# Sheet_2.net
KiCad netlist of a schematic drawn in EasyEDA
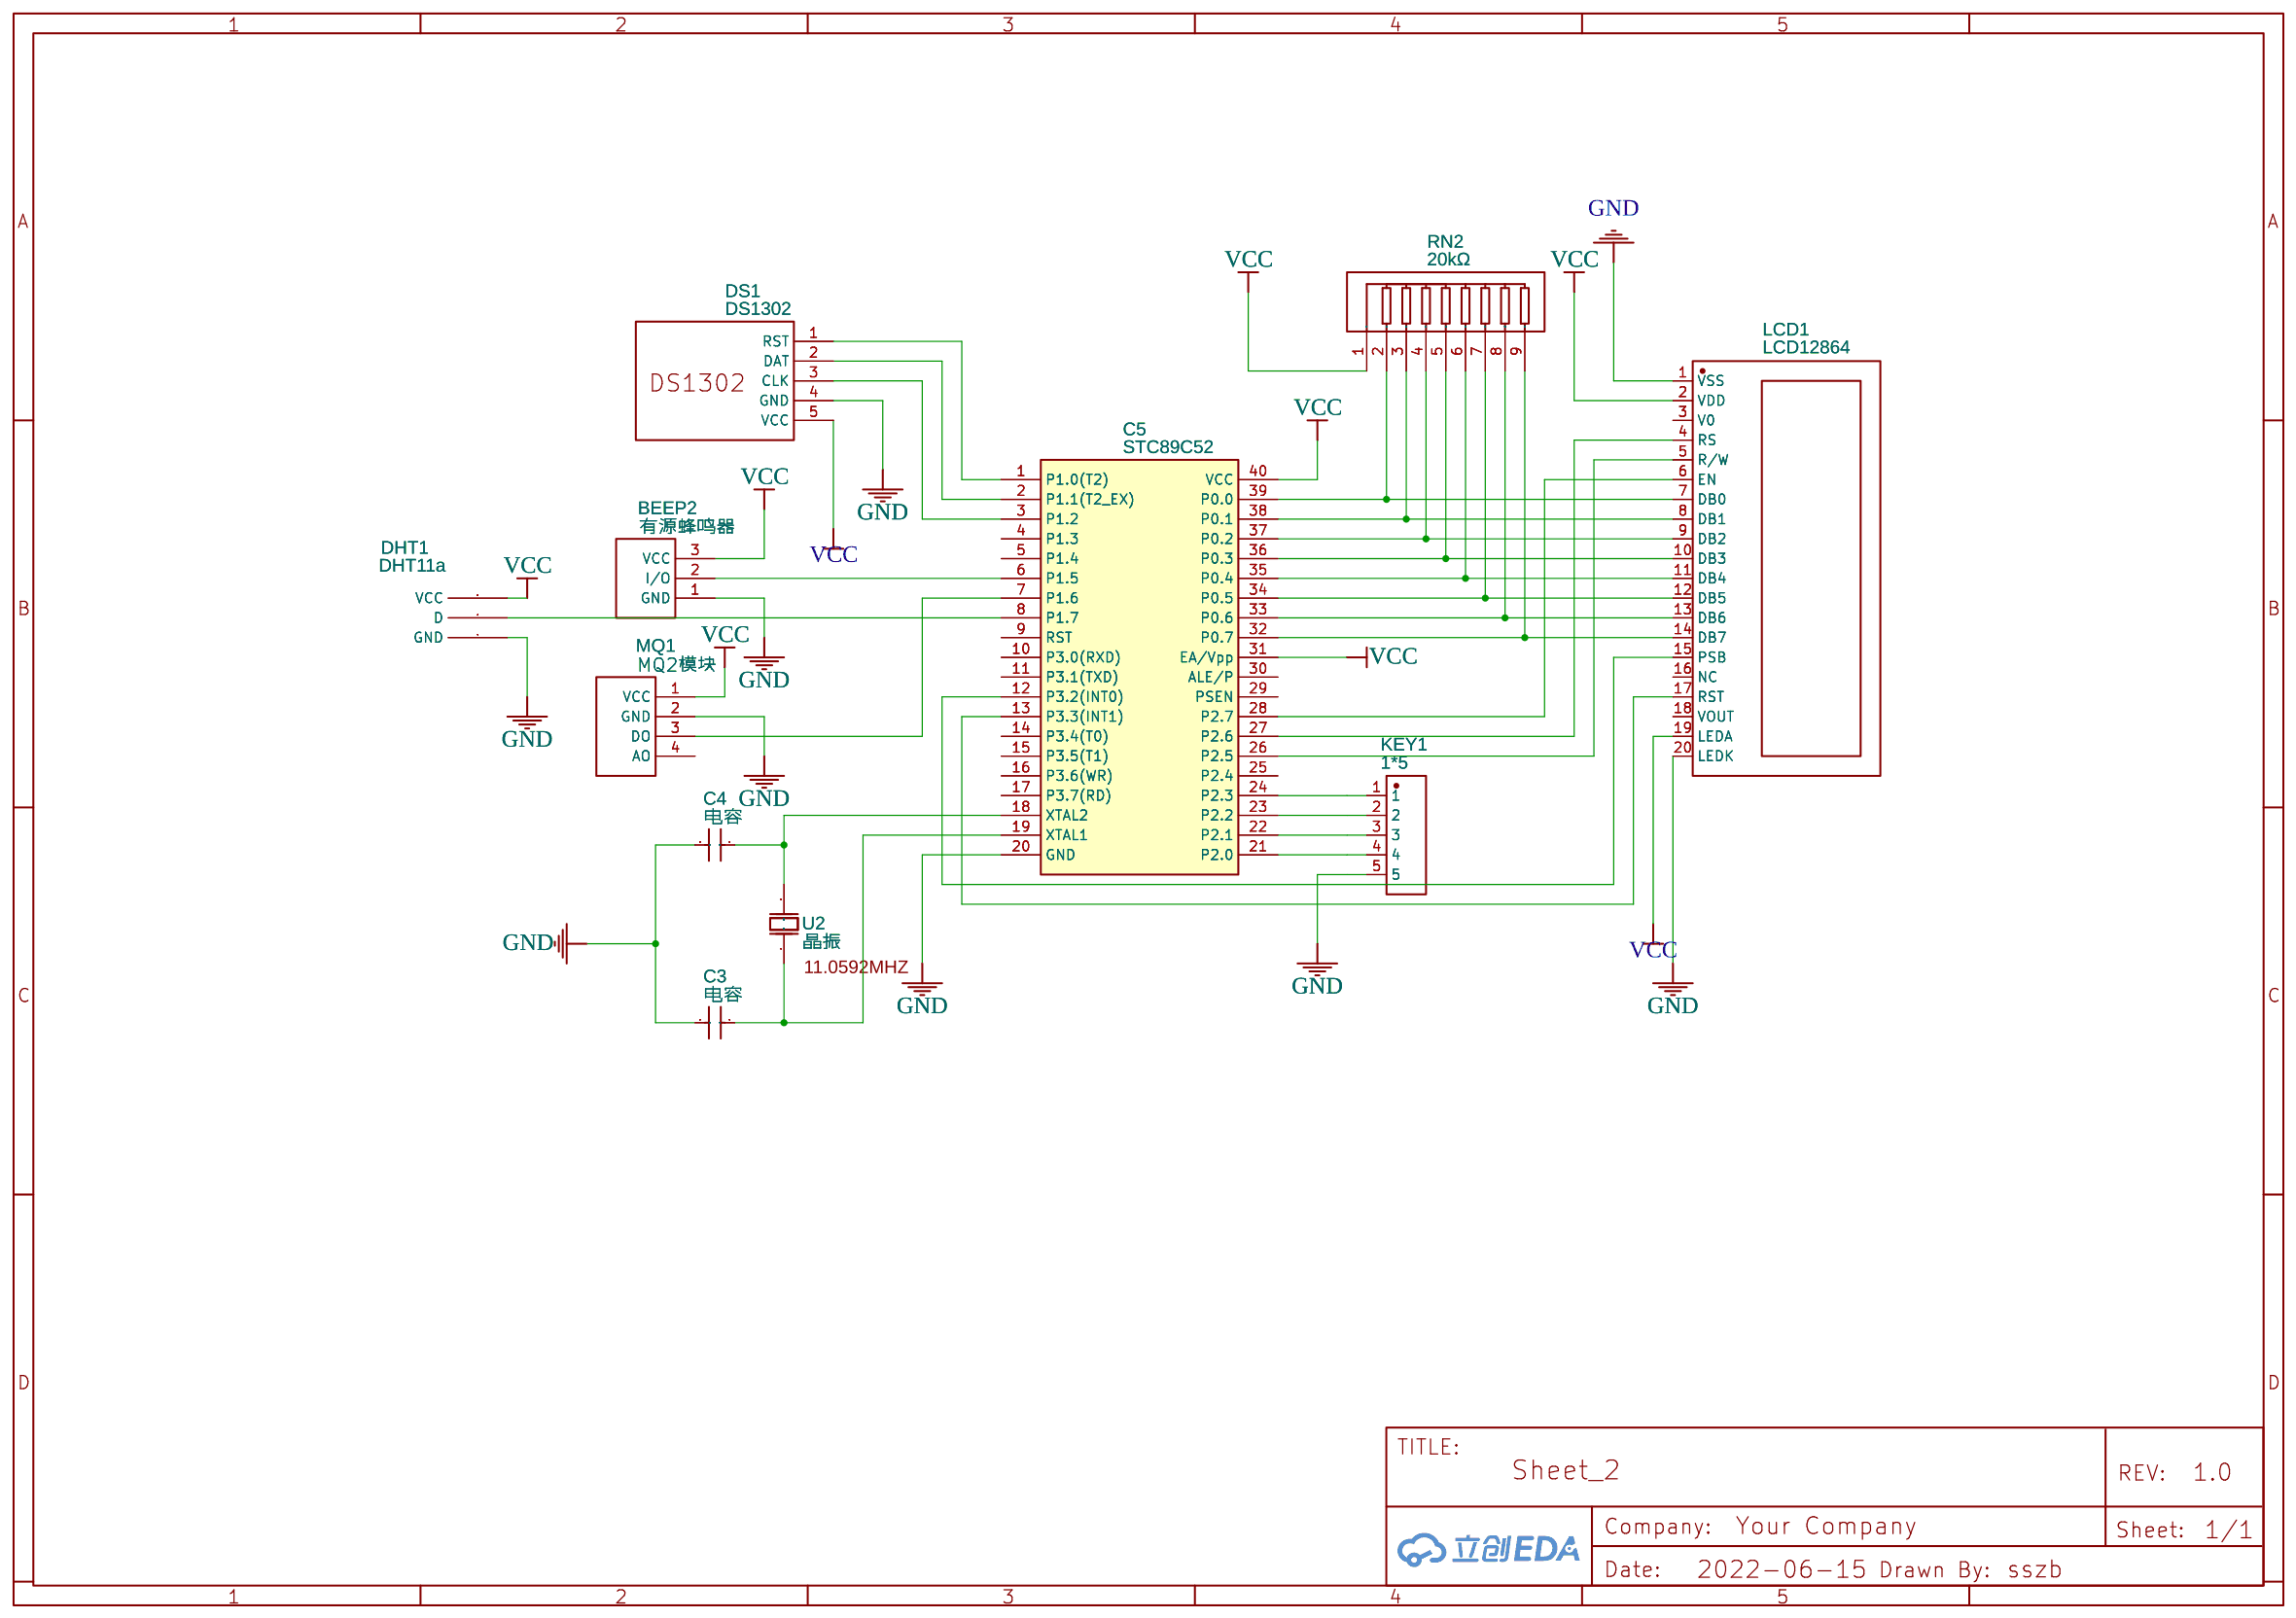
[diagram p0: schematic sheet]

(export (version "E")
  (design (tool "Eeschema 10.0.6"))
  (components
    (comp (ref "BEEP2") (value "有源蜂鸣器") (libsource (lib "") (part "有源蜂鸣器")))
    (comp (ref "C3") (value "电容") (libsource (lib "") (part "电容")))
    (comp (ref "C4") (value "电容") (libsource (lib "") (part "电容")))
    (comp (ref "C5") (value "STC89C52") (libsource (lib "") (part "STC89C52")))
    (comp (ref "DHT1")
      (value "DHT11a")
      (fields (field (name "BOM_Manufacturer Part") "模块DHT11开关模块模块DHT11度温湿湿度度传感器模块温湿"))
      (libsource (lib "") (part "温湿度传感器DHT11a"))
    )
    (comp (ref "DS1") (value "DS1302") (libsource (lib "") (part "DS1302")))
    (comp (ref "KEY1") (value "1*5") (libsource (lib "") (part "1*5")))
    (comp (ref "LCD1") (value "LCD12864") (libsource (lib "") (part "LCD12864")))
    (comp (ref "MQ1") (value "MQ2模块") (libsource (lib "") (part "MQ2模块")))
    (comp (ref "RN2")
      (value "20kΩ")
      (fields (field (name "BOM_Manufacturer Part") "A09-203JP") (field (name "BOM_Supplier Part") "C30847"))
      (libsource (lib "") (part "排阻"))
    )
    (comp (ref "U2") (value "晶振") (libsource (lib "") (part "晶振")))
  )
  (nets
    (net (code "1") (name "GND") (class "Default")
      (node (ref "BEEP2") (pin "1") (pinfunction "GND_1") (pintype "unspecified"))
      (node (ref "C3") (pin "1") (pinfunction "1_1") (pintype "unspecified"))
      (node (ref "C4") (pin "1") (pinfunction "1_1") (pintype "unspecified"))
      (node (ref "C5") (pin "20") (pinfunction "GND_20") (pintype "unspecified"))
      (node (ref "DHT1") (pin "1") (pinfunction "GND_1") (pintype "unspecified"))
      (node (ref "DS1") (pin "4") (pinfunction "GND_4") (pintype "unspecified"))
      (node (ref "KEY1") (pin "5") (pinfunction "5_5") (pintype "unspecified"))
      (node (ref "LCD1") (pin "1") (pinfunction "VSS_1") (pintype "unspecified"))
      (node (ref "LCD1") (pin "20") (pinfunction "LEDK_20") (pintype "unspecified"))
      (node (ref "MQ1") (pin "2") (pinfunction "GND_2") (pintype "unspecified"))
    )
    (net (code "2") (name "Net-(BEEP2-I{slash}O)") (class "Default")
      (node (ref "BEEP2") (pin "2") (pinfunction "I/O_2") (pintype "unspecified"))
      (node (ref "C5") (pin "6") (pinfunction "P1.5_6") (pintype "unspecified"))
    )
    (net (code "3") (name "Net-(C5-P0.0)") (class "Default")
      (node (ref "C5") (pin "39") (pinfunction "P0.0_39") (pintype "unspecified"))
      (node (ref "LCD1") (pin "7") (pinfunction "DB0_7") (pintype "unspecified"))
      (node (ref "RN2") (pin "2") (pinfunction "2_2") (pintype "unspecified"))
    )
    (net (code "4") (name "Net-(C5-P0.1)") (class "Default")
      (node (ref "C5") (pin "38") (pinfunction "P0.1_38") (pintype "unspecified"))
      (node (ref "LCD1") (pin "8") (pinfunction "DB1_8") (pintype "unspecified"))
      (node (ref "RN2") (pin "3") (pinfunction "3_3") (pintype "unspecified"))
    )
    (net (code "5") (name "Net-(C5-P0.2)") (class "Default")
      (node (ref "C5") (pin "37") (pinfunction "P0.2_37") (pintype "unspecified"))
      (node (ref "LCD1") (pin "9") (pinfunction "DB2_9") (pintype "unspecified"))
      (node (ref "RN2") (pin "4") (pinfunction "4_4") (pintype "unspecified"))
    )
    (net (code "6") (name "Net-(C5-P0.3)") (class "Default")
      (node (ref "C5") (pin "36") (pinfunction "P0.3_36") (pintype "unspecified"))
      (node (ref "LCD1") (pin "10") (pinfunction "DB3_10") (pintype "unspecified"))
      (node (ref "RN2") (pin "5") (pinfunction "5_5") (pintype "unspecified"))
    )
    (net (code "7") (name "Net-(C5-P0.4)") (class "Default")
      (node (ref "C5") (pin "35") (pinfunction "P0.4_35") (pintype "unspecified"))
      (node (ref "LCD1") (pin "11") (pinfunction "DB4_11") (pintype "unspecified"))
      (node (ref "RN2") (pin "6") (pinfunction "6_6") (pintype "unspecified"))
    )
    (net (code "8") (name "Net-(C5-P0.5)") (class "Default")
      (node (ref "C5") (pin "34") (pinfunction "P0.5_34") (pintype "unspecified"))
      (node (ref "LCD1") (pin "12") (pinfunction "DB5_12") (pintype "unspecified"))
      (node (ref "RN2") (pin "7") (pinfunction "7_7") (pintype "unspecified"))
    )
    (net (code "9") (name "Net-(C5-P0.6)") (class "Default")
      (node (ref "C5") (pin "33") (pinfunction "P0.6_33") (pintype "unspecified"))
      (node (ref "LCD1") (pin "13") (pinfunction "DB6_13") (pintype "unspecified"))
      (node (ref "RN2") (pin "8") (pinfunction "8_8") (pintype "unspecified"))
    )
    (net (code "10") (name "Net-(C5-P0.7)") (class "Default")
      (node (ref "C5") (pin "32") (pinfunction "P0.7_32") (pintype "unspecified"))
      (node (ref "LCD1") (pin "14") (pinfunction "DB7_14") (pintype "unspecified"))
      (node (ref "RN2") (pin "9") (pinfunction "9_9") (pintype "unspecified"))
    )
    (net (code "11") (name "Net-(C5-P1.0(T2))") (class "Default")
      (node (ref "C5") (pin "1") (pinfunction "P1.0(T2)_1") (pintype "unspecified"))
      (node (ref "DS1") (pin "1") (pinfunction "RST_1") (pintype "unspecified"))
    )
    (net (code "12") (name "Net-(C5-P1.1(T2_EX))") (class "Default")
      (node (ref "C5") (pin "2") (pinfunction "P1.1(T2_EX)_2") (pintype "unspecified"))
      (node (ref "DS1") (pin "2") (pinfunction "DAT_2") (pintype "unspecified"))
    )
    (net (code "13") (name "Net-(C5-P1.2)") (class "Default")
      (node (ref "C5") (pin "3") (pinfunction "P1.2_3") (pintype "unspecified"))
      (node (ref "DS1") (pin "3") (pinfunction "CLK_3") (pintype "unspecified"))
    )
    (net (code "14") (name "Net-(C5-P1.6)") (class "Default")
      (node (ref "C5") (pin "7") (pinfunction "P1.6_7") (pintype "unspecified"))
      (node (ref "MQ1") (pin "3") (pinfunction "DO_3") (pintype "unspecified"))
    )
    (net (code "15") (name "Net-(C5-P1.7)") (class "Default")
      (node (ref "C5") (pin "8") (pinfunction "P1.7_8") (pintype "unspecified"))
      (node (ref "DHT1") (pin "2") (pinfunction "D_2") (pintype "unspecified"))
    )
    (net (code "16") (name "Net-(C5-P2.0)") (class "Default")
      (node (ref "C5") (pin "21") (pinfunction "P2.0_21") (pintype "unspecified"))
      (node (ref "KEY1") (pin "4") (pinfunction "4_4") (pintype "unspecified"))
    )
    (net (code "17") (name "Net-(C5-P2.1)") (class "Default")
      (node (ref "C5") (pin "22") (pinfunction "P2.1_22") (pintype "unspecified"))
      (node (ref "KEY1") (pin "3") (pinfunction "3_3") (pintype "unspecified"))
    )
    (net (code "18") (name "Net-(C5-P2.2)") (class "Default")
      (node (ref "C5") (pin "23") (pinfunction "P2.2_23") (pintype "unspecified"))
      (node (ref "KEY1") (pin "2") (pinfunction "2_2") (pintype "unspecified"))
    )
    (net (code "19") (name "Net-(C5-P2.3)") (class "Default")
      (node (ref "C5") (pin "24") (pinfunction "P2.3_24") (pintype "unspecified"))
      (node (ref "KEY1") (pin "1") (pinfunction "1_1") (pintype "unspecified"))
    )
    (net (code "20") (name "Net-(C5-P2.5)") (class "Default")
      (node (ref "C5") (pin "26") (pinfunction "P2.5_26") (pintype "unspecified"))
      (node (ref "LCD1") (pin "5") (pinfunction "R/W_5") (pintype "unspecified"))
    )
    (net (code "21") (name "Net-(C5-P2.6)") (class "Default")
      (node (ref "C5") (pin "27") (pinfunction "P2.6_27") (pintype "unspecified"))
      (node (ref "LCD1") (pin "4") (pinfunction "RS_4") (pintype "unspecified"))
    )
    (net (code "22") (name "Net-(C5-P2.7)") (class "Default")
      (node (ref "C5") (pin "28") (pinfunction "P2.7_28") (pintype "unspecified"))
      (node (ref "LCD1") (pin "6") (pinfunction "EN_6") (pintype "unspecified"))
    )
    (net (code "23") (name "Net-(C5-P3.2(INT0))") (class "Default")
      (node (ref "C5") (pin "12") (pinfunction "P3.2(INT0)_12") (pintype "unspecified"))
      (node (ref "LCD1") (pin "15") (pinfunction "PSB_15") (pintype "unspecified"))
    )
    (net (code "24") (name "Net-(C5-P3.3(INT1))") (class "Default")
      (node (ref "C5") (pin "13") (pinfunction "P3.3(INT1)_13") (pintype "unspecified"))
      (node (ref "LCD1") (pin "17") (pinfunction "RST_17") (pintype "unspecified"))
    )
    (net (code "25") (name "Net-(C5-XTAL1)") (class "Default")
      (node (ref "C3") (pin "2") (pinfunction "2_2") (pintype "unspecified"))
      (node (ref "C5") (pin "19") (pinfunction "XTAL1_19") (pintype "unspecified"))
      (node (ref "U2") (pin "2") (pinfunction "OSC1_2") (pintype "input"))
    )
    (net (code "26") (name "Net-(C5-XTAL2)") (class "Default")
      (node (ref "C4") (pin "2") (pinfunction "2_2") (pintype "unspecified"))
      (node (ref "C5") (pin "18") (pinfunction "XTAL2_18") (pintype "unspecified"))
      (node (ref "U2") (pin "1") (pinfunction "OSC2_1") (pintype "input"))
    )
    (net (code "27") (name "VCC") (class "Default")
      (node (ref "BEEP2") (pin "3") (pinfunction "VCC_3") (pintype "unspecified"))
      (node (ref "C5") (pin "31") (pinfunction "EA/Vpp_31") (pintype "unspecified"))
      (node (ref "C5") (pin "40") (pinfunction "VCC_40") (pintype "unspecified"))
      (node (ref "DHT1") (pin "3") (pinfunction "VCC_3") (pintype "unspecified"))
      (node (ref "DS1") (pin "5") (pinfunction "VCC_5") (pintype "unspecified"))
      (node (ref "LCD1") (pin "19") (pinfunction "LEDA_19") (pintype "unspecified"))
      (node (ref "LCD1") (pin "2") (pinfunction "VDD_2") (pintype "unspecified"))
      (node (ref "MQ1") (pin "1") (pinfunction "VCC_1") (pintype "unspecified"))
      (node (ref "RN2") (pin "1") (pinfunction "1_1") (pintype "unspecified"))
    )
    (net (code "28") (name "unconnected-(C5-ALE{slash}P-Pad30)") (class "Default")
      (node (ref "C5") (pin "30") (pinfunction "ALE/P_30") (pintype "unspecified"))
    )
    (net (code "29") (name "unconnected-(C5-P1.3-Pad4)") (class "Default")
      (node (ref "C5") (pin "4") (pinfunction "P1.3_4") (pintype "unspecified"))
    )
    (net (code "30") (name "unconnected-(C5-P1.4-Pad5)") (class "Default")
      (node (ref "C5") (pin "5") (pinfunction "P1.4_5") (pintype "unspecified"))
    )
    (net (code "31") (name "unconnected-(C5-P2.4-Pad25)") (class "Default")
      (node (ref "C5") (pin "25") (pinfunction "P2.4_25") (pintype "unspecified"))
    )
    (net (code "32") (name "unconnected-(C5-P3.0(RXD)-Pad10)") (class "Default")
      (node (ref "C5") (pin "10") (pinfunction "P3.0(RXD)_10") (pintype "unspecified"))
    )
    (net (code "33") (name "unconnected-(C5-P3.1(TXD)-Pad11)") (class "Default")
      (node (ref "C5") (pin "11") (pinfunction "P3.1(TXD)_11") (pintype "unspecified"))
    )
    (net (code "34") (name "unconnected-(C5-P3.4(T0)-Pad14)") (class "Default")
      (node (ref "C5") (pin "14") (pinfunction "P3.4(T0)_14") (pintype "unspecified"))
    )
    (net (code "35") (name "unconnected-(C5-P3.5(T1)-Pad15)") (class "Default")
      (node (ref "C5") (pin "15") (pinfunction "P3.5(T1)_15") (pintype "unspecified"))
    )
    (net (code "36") (name "unconnected-(C5-P3.6(WR)-Pad16)") (class "Default")
      (node (ref "C5") (pin "16") (pinfunction "P3.6(WR)_16") (pintype "unspecified"))
    )
    (net (code "37") (name "unconnected-(C5-P3.7(RD)-Pad17)") (class "Default")
      (node (ref "C5") (pin "17") (pinfunction "P3.7(RD)_17") (pintype "unspecified"))
    )
    (net (code "38") (name "unconnected-(C5-PSEN-Pad29)") (class "Default")
      (node (ref "C5") (pin "29") (pinfunction "PSEN_29") (pintype "unspecified"))
    )
    (net (code "39") (name "unconnected-(C5-RST-Pad9)") (class "Default")
      (node (ref "C5") (pin "9") (pinfunction "RST_9") (pintype "unspecified"))
    )
    (net (code "40") (name "unconnected-(LCD1-NC-Pad16)") (class "Default")
      (node (ref "LCD1") (pin "16") (pinfunction "NC_16") (pintype "unspecified"))
    )
    (net (code "41") (name "unconnected-(LCD1-V0-Pad3)") (class "Default")
      (node (ref "LCD1") (pin "3") (pinfunction "V0_3") (pintype "unspecified"))
    )
    (net (code "42") (name "unconnected-(LCD1-VOUT-Pad18)") (class "Default")
      (node (ref "LCD1") (pin "18") (pinfunction "VOUT_18") (pintype "unspecified"))
    )
    (net (code "43") (name "unconnected-(MQ1-AO-Pad4)") (class "Default")
      (node (ref "MQ1") (pin "4") (pinfunction "AO_4") (pintype "unspecified"))
    )
  )
)
